# PneumatikaDriveSema.net
KiCad netlist of a schematic drawn in Altium Designer
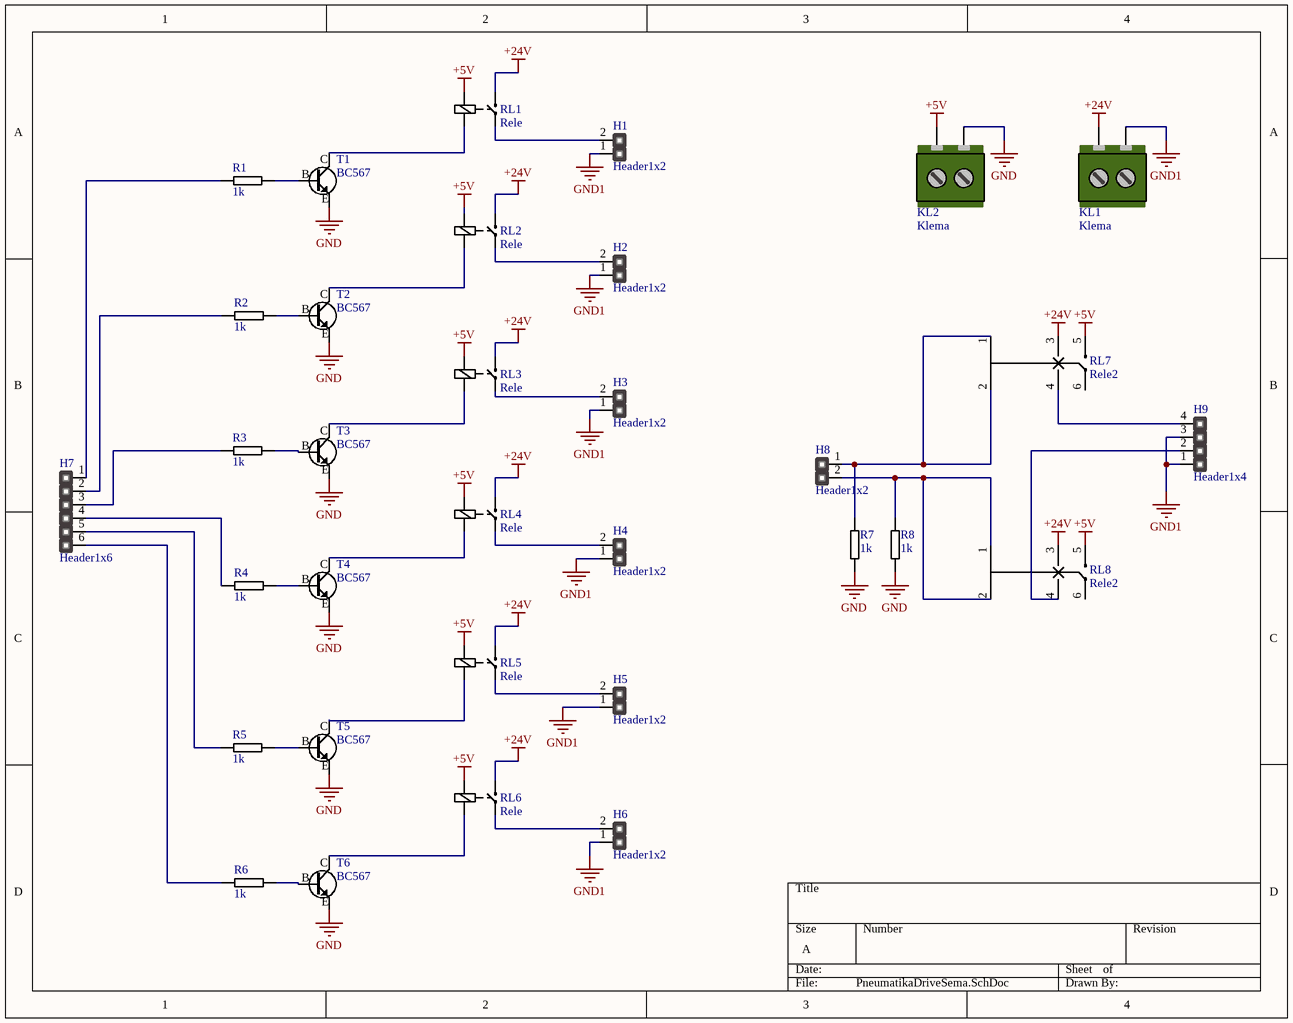
[diagram p0: PneumatikaDriveSema.SchDoc]

(export (version "E")
  (design (tool "Eeschema 10.0.6"))
  (components
    (comp (ref "H1")
      (value "Header1x2")
      (footprint "Header1x2")
      (libsource (lib "KILEX LIB SCH") (part "Header1x2"))
    )
    (comp (ref "H2")
      (value "Header1x2")
      (footprint "Header1x2")
      (libsource (lib "KILEX LIB SCH") (part "Header1x2"))
    )
    (comp (ref "H3")
      (value "Header1x2")
      (footprint "Header1x2")
      (libsource (lib "KILEX LIB SCH") (part "Header1x2"))
    )
    (comp (ref "H4")
      (value "Header1x2")
      (footprint "Header1x2")
      (libsource (lib "KILEX LIB SCH") (part "Header1x2"))
    )
    (comp (ref "H5")
      (value "Header1x2")
      (footprint "Header1x2")
      (libsource (lib "KILEX LIB SCH") (part "Header1x2"))
    )
    (comp (ref "H6")
      (value "Header1x2")
      (footprint "Header1x2")
      (libsource (lib "KILEX LIB SCH") (part "Header1x2"))
    )
    (comp (ref "H7")
      (value "Header1x6")
      (footprint "Header1x6")
      (libsource (lib "KILEX LIB SCH") (part "Header1x6"))
    )
    (comp (ref "H8") (value "Header1x2") (footprint "Header1x2") (libsource (lib "") (part "Header1x2_1")))
    (comp (ref "H9")
      (value "Header1x4")
      (footprint "Header1x4")
      (libsource (lib "KILEX LIB SCH") (part "Header1x4"))
    )
    (comp (ref "KL1") (value "Klema") (footprint "Klema") (libsource (lib "KILEX LIB SCH") (part "Klema")))
    (comp (ref "KL2") (value "Klema") (footprint "Klema") (libsource (lib "KILEX LIB SCH") (part "Klema")))
    (comp (ref "R1") (value "1k") (footprint "R1(300milsa)") (libsource (lib "KILEX LIB SCH") (part "R1")))
    (comp (ref "R2") (value "1k") (footprint "R1(300milsa)") (libsource (lib "KILEX LIB SCH") (part "R1")))
    (comp (ref "R3") (value "1k") (footprint "R1(300milsa)") (libsource (lib "KILEX LIB SCH") (part "R1")))
    (comp (ref "R4") (value "1k") (footprint "R1(300milsa)") (libsource (lib "KILEX LIB SCH") (part "R1")))
    (comp (ref "R5") (value "1k") (footprint "R1(300milsa)") (libsource (lib "KILEX LIB SCH") (part "R1")))
    (comp (ref "R6") (value "1k") (footprint "R1(300milsa)") (libsource (lib "KILEX LIB SCH") (part "R1")))
    (comp (ref "R7") (value "1k") (footprint "R1(300milsa)") (libsource (lib "KILEX LIB SCH") (part "R1")))
    (comp (ref "R8") (value "1k") (footprint "R1(300milsa)") (libsource (lib "KILEX LIB SCH") (part "R1")))
    (comp (ref "RL1") (value "Rele") (footprint "Rele(MD-5)") (libsource (lib "KILEX LIB SCH") (part "Rele")))
    (comp (ref "RL2") (value "Rele") (footprint "Rele(MD-5)") (libsource (lib "KILEX LIB SCH") (part "Rele")))
    (comp (ref "RL3") (value "Rele") (footprint "Rele(MD-5)") (libsource (lib "KILEX LIB SCH") (part "Rele")))
    (comp (ref "RL4") (value "Rele") (footprint "Rele(MD-5)") (libsource (lib "KILEX LIB SCH") (part "Rele")))
    (comp (ref "RL5") (value "Rele") (footprint "Rele(MD-5)") (libsource (lib "KILEX LIB SCH") (part "Rele")))
    (comp (ref "RL6") (value "Rele") (footprint "Rele(MD-5)") (libsource (lib "KILEX LIB SCH") (part "Rele")))
    (comp (ref "RL7")
      (value "Rele2")
      (footprint "Rele(thu 24-03)")
      (libsource (lib "KILEX LIB SCH") (part "Rele2"))
    )
    (comp (ref "RL8")
      (value "Rele2")
      (footprint "Rele(thu 24-03)")
      (libsource (lib "KILEX LIB SCH") (part "Rele2"))
    )
    (comp (ref "T1")
      (value "BC567")
      (footprint "TO-92")
      (libsource (lib "KILEX LIB SCH") (part "Transistor NPN"))
    )
    (comp (ref "T2")
      (value "BC567")
      (footprint "TO-92")
      (libsource (lib "KILEX LIB SCH") (part "Transistor NPN"))
    )
    (comp (ref "T3")
      (value "BC567")
      (footprint "TO-92")
      (libsource (lib "KILEX LIB SCH") (part "Transistor NPN"))
    )
    (comp (ref "T4")
      (value "BC567")
      (footprint "TO-92")
      (libsource (lib "KILEX LIB SCH") (part "Transistor NPN"))
    )
    (comp (ref "T5")
      (value "BC567")
      (footprint "TO-92")
      (libsource (lib "KILEX LIB SCH") (part "Transistor NPN"))
    )
    (comp (ref "T6")
      (value "BC567")
      (footprint "TO-92")
      (libsource (lib "KILEX LIB SCH") (part "Transistor NPN"))
    )
  )
  (nets
    (net (code "1") (name "+5V") (class "Default")
      (node (ref "KL2") (pin "2") (pinfunction "2_2") (pintype "passive"))
      (node (ref "RL1") (pin "2") (pinfunction "2_2") (pintype "passive"))
      (node (ref "RL2") (pin "2") (pinfunction "2_2") (pintype "passive"))
      (node (ref "RL3") (pin "2") (pinfunction "2_2") (pintype "passive"))
      (node (ref "RL4") (pin "2") (pinfunction "2_2") (pintype "passive"))
      (node (ref "RL5") (pin "2") (pinfunction "2_2") (pintype "passive"))
      (node (ref "RL6") (pin "2") (pinfunction "2_2") (pintype "passive"))
      (node (ref "RL7") (pin "5") (pinfunction "5_5") (pintype "passive"))
      (node (ref "RL8") (pin "5") (pinfunction "5_5") (pintype "passive"))
    )
    (net (code "2") (name "+24V") (class "Default")
      (node (ref "KL1") (pin "2") (pinfunction "2_2") (pintype "passive"))
      (node (ref "RL1") (pin "4") (pinfunction "4_4") (pintype "passive"))
      (node (ref "RL2") (pin "4") (pinfunction "4_4") (pintype "passive"))
      (node (ref "RL3") (pin "4") (pinfunction "4_4") (pintype "passive"))
      (node (ref "RL4") (pin "4") (pinfunction "4_4") (pintype "passive"))
      (node (ref "RL5") (pin "4") (pinfunction "4_4") (pintype "passive"))
      (node (ref "RL6") (pin "4") (pinfunction "4_4") (pintype "passive"))
      (node (ref "RL7") (pin "3") (pinfunction "3_3") (pintype "passive"))
      (node (ref "RL8") (pin "3") (pinfunction "3_3") (pintype "passive"))
    )
    (net (code "3") (name "GND") (class "Default")
      (node (ref "KL2") (pin "1") (pinfunction "1_1") (pintype "passive"))
      (node (ref "R7") (pin "1") (pinfunction "1_1") (pintype "passive"))
      (node (ref "R8") (pin "1") (pinfunction "1_1") (pintype "passive"))
      (node (ref "T1") (pin "2") (pinfunction "2_2") (pintype "passive"))
      (node (ref "T2") (pin "2") (pinfunction "2_2") (pintype "passive"))
      (node (ref "T3") (pin "2") (pinfunction "2_2") (pintype "passive"))
      (node (ref "T4") (pin "2") (pinfunction "2_2") (pintype "passive"))
      (node (ref "T5") (pin "2") (pinfunction "2_2") (pintype "passive"))
    )
    (net (code "4") (name "GND1") (class "Default")
      (node (ref "H1") (pin "1") (pinfunction "1_1") (pintype "passive"))
      (node (ref "H2") (pin "1") (pinfunction "1_1") (pintype "passive"))
      (node (ref "H3") (pin "1") (pinfunction "1_1") (pintype "passive"))
      (node (ref "H4") (pin "1") (pinfunction "1_1") (pintype "passive"))
      (node (ref "H5") (pin "1") (pinfunction "1_1") (pintype "passive"))
      (node (ref "H6") (pin "1") (pinfunction "1_1") (pintype "passive"))
      (node (ref "H9") (pin "1") (pinfunction "1_1") (pintype "passive"))
      (node (ref "H9") (pin "3") (pinfunction "3_3") (pintype "passive"))
      (node (ref "KL1") (pin "1") (pinfunction "1_1") (pintype "passive"))
    )
    (net (code "5") (name "Net-(H1-Pad2)") (class "Default")
      (node (ref "H1") (pin "2") (pinfunction "2_2") (pintype "passive"))
      (node (ref "RL1") (pin "3") (pinfunction "3_3") (pintype "passive"))
    )
    (net (code "6") (name "Net-(H2-Pad2)") (class "Default")
      (node (ref "H2") (pin "2") (pinfunction "2_2") (pintype "passive"))
      (node (ref "RL2") (pin "3") (pinfunction "3_3") (pintype "passive"))
    )
    (net (code "7") (name "Net-(H3-Pad2)") (class "Default")
      (node (ref "H3") (pin "2") (pinfunction "2_2") (pintype "passive"))
      (node (ref "RL3") (pin "3") (pinfunction "3_3") (pintype "passive"))
    )
    (net (code "8") (name "Net-(H4-Pad2)") (class "Default")
      (node (ref "H4") (pin "2") (pinfunction "2_2") (pintype "passive"))
      (node (ref "RL4") (pin "3") (pinfunction "3_3") (pintype "passive"))
    )
    (net (code "9") (name "Net-(H5-Pad2)") (class "Default")
      (node (ref "H5") (pin "2") (pinfunction "2_2") (pintype "passive"))
      (node (ref "RL5") (pin "3") (pinfunction "3_3") (pintype "passive"))
    )
    (net (code "10") (name "Net-(H6-Pad2)") (class "Default")
      (node (ref "H6") (pin "2") (pinfunction "2_2") (pintype "passive"))
      (node (ref "RL6") (pin "3") (pinfunction "3_3") (pintype "passive"))
    )
    (net (code "11") (name "Net-(H7-Pad1)") (class "Default")
      (node (ref "H7") (pin "1") (pinfunction "1_1") (pintype "passive"))
      (node (ref "R1") (pin "1") (pinfunction "1_1") (pintype "passive"))
    )
    (net (code "12") (name "Net-(H7-Pad2)") (class "Default")
      (node (ref "H7") (pin "2") (pinfunction "2_2") (pintype "passive"))
      (node (ref "R2") (pin "1") (pinfunction "1_1") (pintype "passive"))
    )
    (net (code "13") (name "Net-(H7-Pad3)") (class "Default")
      (node (ref "H7") (pin "3") (pinfunction "3_3") (pintype "passive"))
      (node (ref "R3") (pin "1") (pinfunction "1_1") (pintype "passive"))
    )
    (net (code "14") (name "Net-(H7-Pad4)") (class "Default")
      (node (ref "H7") (pin "4") (pinfunction "4_4") (pintype "passive"))
      (node (ref "R4") (pin "1") (pinfunction "1_1") (pintype "passive"))
    )
    (net (code "15") (name "Net-(H7-Pad5)") (class "Default")
      (node (ref "H7") (pin "5") (pinfunction "5_5") (pintype "passive"))
      (node (ref "R5") (pin "1") (pinfunction "1_1") (pintype "passive"))
    )
    (net (code "16") (name "Net-(H7-Pad6)") (class "Default")
      (node (ref "H7") (pin "6") (pinfunction "6_6") (pintype "passive"))
      (node (ref "R6") (pin "1") (pinfunction "1_1") (pintype "passive"))
    )
    (net (code "17") (name "Net-(H8-Pad1)") (class "Default")
      (node (ref "H8") (pin "1") (pinfunction "1_1") (pintype "passive"))
      (node (ref "R7") (pin "2") (pinfunction "2_2") (pintype "passive"))
      (node (ref "RL7") (pin "1") (pinfunction "1_1") (pintype "passive"))
      (node (ref "RL7") (pin "2") (pinfunction "2_2") (pintype "passive"))
    )
    (net (code "18") (name "Net-(H8-Pad2)") (class "Default")
      (node (ref "H8") (pin "2") (pinfunction "2_2") (pintype "passive"))
      (node (ref "R8") (pin "2") (pinfunction "2_2") (pintype "passive"))
      (node (ref "RL8") (pin "1") (pinfunction "1_1") (pintype "passive"))
      (node (ref "RL8") (pin "2") (pinfunction "2_2") (pintype "passive"))
    )
    (net (code "19") (name "Net-(H9-Pad2)") (class "Default")
      (node (ref "H9") (pin "2") (pinfunction "2_2") (pintype "passive"))
      (node (ref "RL8") (pin "4") (pinfunction "4_4") (pintype "passive"))
    )
    (net (code "20") (name "Net-(H9-Pad4)") (class "Default")
      (node (ref "H9") (pin "4") (pinfunction "4_4") (pintype "passive"))
      (node (ref "RL7") (pin "4") (pinfunction "4_4") (pintype "passive"))
    )
    (net (code "21") (name "Net-(R1-Pad2)") (class "Default")
      (node (ref "R1") (pin "2") (pinfunction "2_2") (pintype "passive"))
      (node (ref "T1") (pin "1") (pinfunction "1_1") (pintype "passive"))
    )
    (net (code "22") (name "Net-(R2-Pad2)") (class "Default")
      (node (ref "R2") (pin "2") (pinfunction "2_2") (pintype "passive"))
      (node (ref "T2") (pin "1") (pinfunction "1_1") (pintype "passive"))
    )
    (net (code "23") (name "Net-(R3-Pad2)") (class "Default")
      (node (ref "R3") (pin "2") (pinfunction "2_2") (pintype "passive"))
      (node (ref "T3") (pin "1") (pinfunction "1_1") (pintype "passive"))
    )
    (net (code "24") (name "Net-(R4-Pad2)") (class "Default")
      (node (ref "R4") (pin "2") (pinfunction "2_2") (pintype "passive"))
      (node (ref "T4") (pin "1") (pinfunction "1_1") (pintype "passive"))
    )
    (net (code "25") (name "Net-(R5-Pad2)") (class "Default")
      (node (ref "R5") (pin "2") (pinfunction "2_2") (pintype "passive"))
      (node (ref "T5") (pin "1") (pinfunction "1_1") (pintype "passive"))
    )
    (net (code "26") (name "Net-(R6-Pad2)") (class "Default")
      (node (ref "R6") (pin "2") (pinfunction "2_2") (pintype "passive"))
      (node (ref "T6") (pin "1") (pinfunction "1_1") (pintype "passive"))
    )
    (net (code "27") (name "Net-(RL1-Pad1)") (class "Default")
      (node (ref "RL1") (pin "1") (pinfunction "1_1") (pintype "passive"))
      (node (ref "T1") (pin "3") (pinfunction "3_3") (pintype "passive"))
    )
    (net (code "28") (name "Net-(RL2-Pad1)") (class "Default")
      (node (ref "RL2") (pin "1") (pinfunction "1_1") (pintype "passive"))
      (node (ref "T2") (pin "3") (pinfunction "3_3") (pintype "passive"))
    )
    (net (code "29") (name "Net-(RL3-Pad1)") (class "Default")
      (node (ref "RL3") (pin "1") (pinfunction "1_1") (pintype "passive"))
      (node (ref "T3") (pin "3") (pinfunction "3_3") (pintype "passive"))
    )
    (net (code "30") (name "Net-(RL4-Pad1)") (class "Default")
      (node (ref "RL4") (pin "1") (pinfunction "1_1") (pintype "passive"))
      (node (ref "T4") (pin "3") (pinfunction "3_3") (pintype "passive"))
    )
    (net (code "31") (name "Net-(RL5-Pad1)") (class "Default")
      (node (ref "RL5") (pin "1") (pinfunction "1_1") (pintype "passive"))
      (node (ref "T5") (pin "3") (pinfunction "3_3") (pintype "passive"))
    )
    (net (code "32") (name "Net-(RL6-Pad1)") (class "Default")
      (node (ref "RL6") (pin "1") (pinfunction "1_1") (pintype "passive"))
      (node (ref "T6") (pin "3") (pinfunction "3_3") (pintype "passive"))
    )
    (net (code "33") (name "unconnected-(RL7-Pad6)") (class "Default")
      (node (ref "RL7") (pin "6") (pinfunction "6_6") (pintype "passive"))
    )
    (net (code "34") (name "unconnected-(RL8-Pad6)") (class "Default")
      (node (ref "RL8") (pin "6") (pinfunction "6_6") (pintype "passive"))
    )
    (net (code "35") (name "unconnected-(T6-Pad2)") (class "Default")
      (node (ref "T6") (pin "2") (pinfunction "2_2") (pintype "passive"))
    )
  )
)
